# Sheet1.net
KiCad netlist of a schematic drawn in Altium Designer
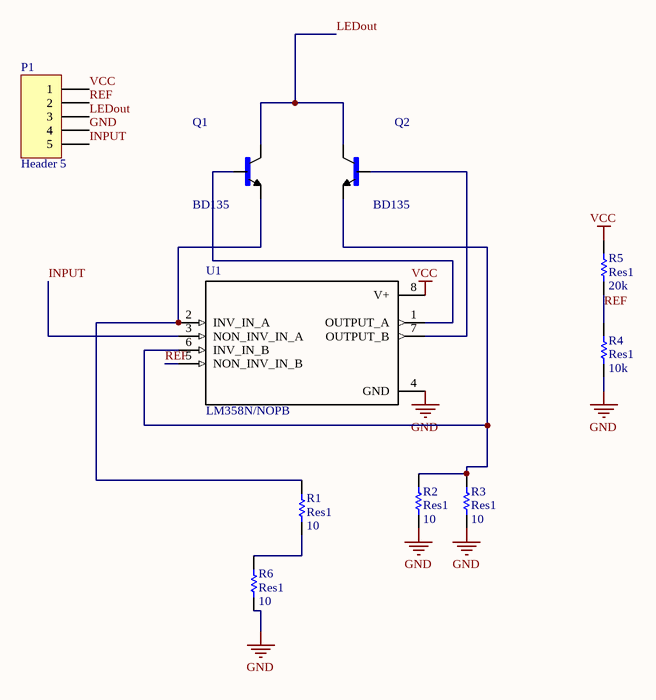
[diagram p0: Sheet1.SchDoc]

(export (version "E")
  (design (tool "Eeschema 10.0.6"))
  (components
    (comp (ref "P1")
      (value "Header 5")
      (footprint "HDR1X5")
      (description "Header, 5-Pin")
      (fields (field (name "PUBLISHER") "Altium Limited"))
      (libsource (lib "Miscellaneous Connectors") (part "Header 5"))
    )
    (comp (ref "Q1")
      (value "BD135")
      (footprint "*TO229P780X300X2000-3")
      (description "Trans GP BJT NPN 45V 1.5A 3-Pin TO-126")
      (fields (field (name "MF") "ON Semiconductor"))
      (libsource (lib "BD135") (part "BD135"))
    )
    (comp (ref "Q2")
      (value "BD135")
      (footprint "*TO229P780X300X2000-3")
      (description "Trans GP BJT NPN 45V 1.5A 3-Pin TO-126")
      (fields (field (name "MF") "ON Semiconductor"))
      (libsource (lib "BD135") (part "BD135"))
    )
    (comp (ref "R1")
      (value "Res1")
      (footprint "AXIAL-0.3")
      (description "Resistor")
      (fields (field (name "ALTIUM_VALUE") "10") (field (name "PUBLISHER") "Altium Limited"))
      (libsource (lib "Miscellaneous Devices") (part "Res1"))
    )
    (comp (ref "R2")
      (value "Res1")
      (footprint "AXIAL-0.3")
      (description "Resistor")
      (fields (field (name "ALTIUM_VALUE") "10") (field (name "PUBLISHER") "Altium Limited"))
      (libsource (lib "Miscellaneous Devices") (part "Res1"))
    )
    (comp (ref "R3")
      (value "Res1")
      (footprint "AXIAL-0.3")
      (description "Resistor")
      (fields (field (name "ALTIUM_VALUE") "10") (field (name "PUBLISHER") "Altium Limited"))
      (libsource (lib "Miscellaneous Devices") (part "Res1"))
    )
    (comp (ref "R4")
      (value "Res1")
      (footprint "AXIAL-0.3")
      (description "Resistor")
      (fields (field (name "ALTIUM_VALUE") "10k") (field (name "PUBLISHER") "Altium Limited"))
      (libsource (lib "Miscellaneous Devices") (part "Res1"))
    )
    (comp (ref "R5")
      (value "Res1")
      (footprint "AXIAL-0.3")
      (description "Resistor")
      (fields (field (name "ALTIUM_VALUE") "20k") (field (name "PUBLISHER") "Altium Limited"))
      (libsource (lib "Miscellaneous Devices") (part "Res1"))
    )
    (comp (ref "R6")
      (value "Res1")
      (footprint "AXIAL-0.3")
      (description "Resistor")
      (fields (field (name "ALTIUM_VALUE") "10") (field (name "PUBLISHER") "Altium Limited"))
      (libsource (lib "Miscellaneous Devices") (part "Res1"))
    )
    (comp (ref "U1")
      (value "LM358N/NOPB")
      (footprint "*DIP794W45P254L1016H508Q8")
      (fields (field (name "MF") "ON Semiconductor") (field (name "MP") "LM358N"))
      (libsource (lib "LM358N_NOPB") (part "LM358N/NOPB"))
    )
  )
  (nets
    (net (code "1") (name "/INPUT") (class "Default")
      (node (ref "P1") (pin "5") (pinfunction "5_5") (pintype "passive"))
      (node (ref "U1") (pin "3") (pinfunction "NON_INV_IN_A_3") (pintype "input"))
    )
    (net (code "2") (name "/LEDout") (class "Default")
      (node (ref "P1") (pin "3") (pinfunction "3_3") (pintype "passive"))
      (node (ref "Q1") (pin "2") (pinfunction "C_2") (pintype "passive"))
      (node (ref "Q2") (pin "2") (pinfunction "C_2") (pintype "passive"))
    )
    (net (code "3") (name "/REF") (class "Default")
      (node (ref "P1") (pin "2") (pinfunction "2_2") (pintype "passive"))
      (node (ref "R4") (pin "2") (pinfunction "2_2") (pintype "passive"))
      (node (ref "R5") (pin "1") (pinfunction "1_1") (pintype "passive"))
      (node (ref "U1") (pin "5") (pinfunction "NON_INV_IN_B_5") (pintype "input"))
    )
    (net (code "4") (name "GND") (class "Default")
      (node (ref "P1") (pin "4") (pinfunction "4_4") (pintype "passive"))
      (node (ref "R2") (pin "1") (pinfunction "1_1") (pintype "passive"))
      (node (ref "R3") (pin "1") (pinfunction "1_1") (pintype "passive"))
      (node (ref "R4") (pin "1") (pinfunction "1_1") (pintype "passive"))
      (node (ref "R6") (pin "1") (pinfunction "1_1") (pintype "passive"))
      (node (ref "U1") (pin "4") (pinfunction "GND_4") (pintype "power_in"))
    )
    (net (code "5") (name "Net-(Q1-B)") (class "Default")
      (node (ref "Q1") (pin "3") (pinfunction "B_3") (pintype "passive"))
      (node (ref "U1") (pin "1") (pinfunction "OUTPUT_A_1") (pintype "output"))
    )
    (net (code "6") (name "Net-(Q1-E)") (class "Default")
      (node (ref "Q1") (pin "1") (pinfunction "E_1") (pintype "passive"))
      (node (ref "R1") (pin "2") (pinfunction "2_2") (pintype "passive"))
      (node (ref "U1") (pin "2") (pinfunction "INV_IN_A_2") (pintype "input"))
    )
    (net (code "7") (name "Net-(Q2-B)") (class "Default")
      (node (ref "Q2") (pin "3") (pinfunction "B_3") (pintype "passive"))
      (node (ref "U1") (pin "7") (pinfunction "OUTPUT_B_7") (pintype "output"))
    )
    (net (code "8") (name "Net-(Q2-E)") (class "Default")
      (node (ref "Q2") (pin "1") (pinfunction "E_1") (pintype "passive"))
      (node (ref "R2") (pin "2") (pinfunction "2_2") (pintype "passive"))
      (node (ref "R3") (pin "2") (pinfunction "2_2") (pintype "passive"))
      (node (ref "U1") (pin "6") (pinfunction "INV_IN_B_6") (pintype "input"))
    )
    (net (code "9") (name "Net-(R1-Pad1)") (class "Default")
      (node (ref "R1") (pin "1") (pinfunction "1_1") (pintype "passive"))
      (node (ref "R6") (pin "2") (pinfunction "2_2") (pintype "passive"))
    )
    (net (code "10") (name "VCC") (class "Default")
      (node (ref "P1") (pin "1") (pinfunction "1_1") (pintype "passive"))
      (node (ref "R5") (pin "2") (pinfunction "2_2") (pintype "passive"))
      (node (ref "U1") (pin "8") (pinfunction "V+_8") (pintype "power_in"))
    )
  )
)
